# beacon.net
KiCad netlist of a schematic drawn in EAGLE
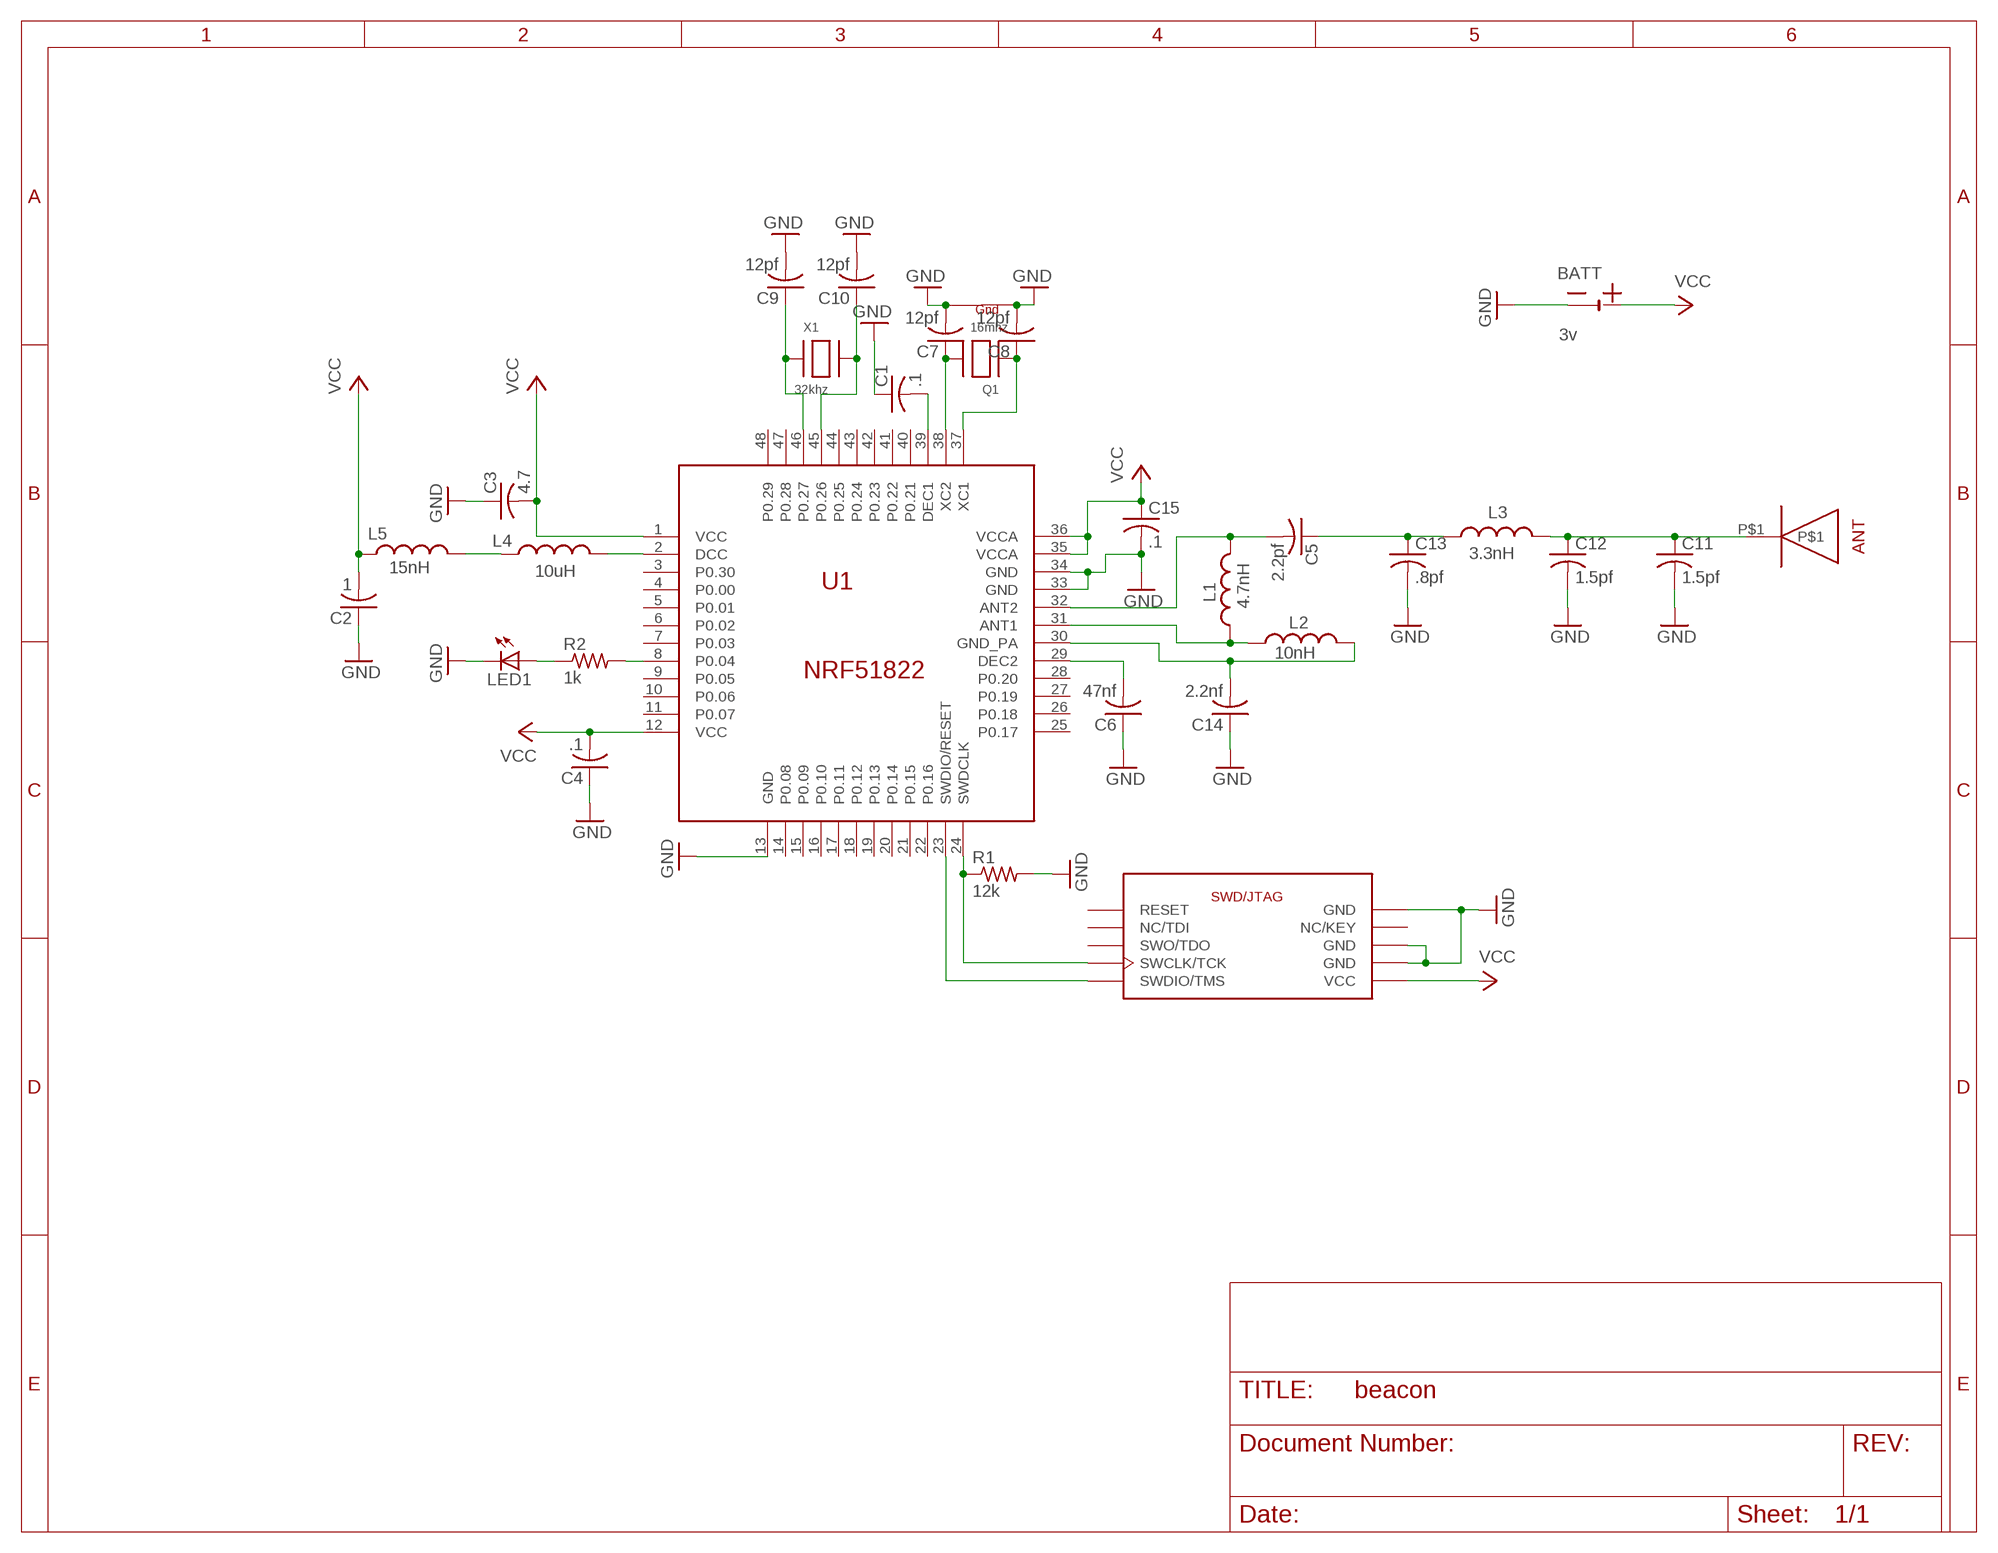
[diagram p0: schematic, sheet 1]

(export (version "E")
  (design (tool "Eeschema 10.0.6"))
  (components
    (comp (ref "BATT")
      (value "3v")
      (footprint "eagle-import:CR2032-SMD")
      (libsource (lib "eagle-import") (part "CR2032SMT"))
    )
    (comp (ref "C1")
      (value ".1")
      (footprint "eagle-import:C0603")
      (libsource (lib "eagle-import") (part "C-USC0603"))
    )
    (comp (ref "C2")
      (value "1")
      (footprint "eagle-import:C0603")
      (libsource (lib "eagle-import") (part "C-USC0603"))
    )
    (comp (ref "C3")
      (value "4.7")
      (footprint "eagle-import:C0603")
      (libsource (lib "eagle-import") (part "C-USC0603"))
    )
    (comp (ref "C4")
      (value ".1")
      (footprint "eagle-import:C0603")
      (libsource (lib "eagle-import") (part "C-USC0603"))
    )
    (comp (ref "C5")
      (value "2.2pf")
      (footprint "eagle-import:C0603")
      (libsource (lib "eagle-import") (part "C-USC0603"))
    )
    (comp (ref "C6")
      (value "47nf")
      (footprint "eagle-import:C0603")
      (libsource (lib "eagle-import") (part "C-USC0603"))
    )
    (comp (ref "C7")
      (value "12pf")
      (footprint "eagle-import:C0603")
      (libsource (lib "eagle-import") (part "C-USC0603"))
    )
    (comp (ref "C8")
      (value "12pf")
      (footprint "eagle-import:C0603")
      (libsource (lib "eagle-import") (part "C-USC0603"))
    )
    (comp (ref "C9")
      (value "12pf")
      (footprint "eagle-import:C0603")
      (libsource (lib "eagle-import") (part "C-USC0603"))
    )
    (comp (ref "C10")
      (value "12pf")
      (footprint "eagle-import:C0603")
      (libsource (lib "eagle-import") (part "C-USC0603"))
    )
    (comp (ref "C11")
      (value "1.5pf")
      (footprint "eagle-import:C0603")
      (libsource (lib "eagle-import") (part "C-USC0603"))
    )
    (comp (ref "C12")
      (value "1.5pf")
      (footprint "eagle-import:C0603")
      (libsource (lib "eagle-import") (part "C-USC0603"))
    )
    (comp (ref "C13")
      (value ".8pf")
      (footprint "eagle-import:C0603")
      (libsource (lib "eagle-import") (part "C-USC0603"))
    )
    (comp (ref "C14")
      (value "2.2nf")
      (footprint "eagle-import:C0603")
      (libsource (lib "eagle-import") (part "C-USC0603"))
    )
    (comp (ref "C15")
      (value ".1")
      (footprint "eagle-import:C0603")
      (libsource (lib "eagle-import") (part "C-USC0603"))
    )
    (comp (ref "L1")
      (value "4.7nH")
      (footprint "eagle-import:0603")
      (libsource (lib "eagle-import") (part "INDUCTOR0603"))
    )
    (comp (ref "L2")
      (value "10nH")
      (footprint "eagle-import:0603")
      (libsource (lib "eagle-import") (part "INDUCTOR0603"))
    )
    (comp (ref "L3")
      (value "3.3nH")
      (footprint "eagle-import:0603")
      (libsource (lib "eagle-import") (part "INDUCTOR0603"))
    )
    (comp (ref "L4")
      (value "10uH")
      (footprint "eagle-import:0603")
      (libsource (lib "eagle-import") (part "INDUCTOR0603"))
    )
    (comp (ref "L5")
      (value "15nH")
      (footprint "eagle-import:0603")
      (libsource (lib "eagle-import") (part "INDUCTOR0603"))
    )
    (comp (ref "LED1")
      (value "LEDCHIP-LED0603")
      (footprint "eagle-import:CHIP-LED0603")
      (libsource (lib "eagle-import") (part "LEDCHIP-LED0603"))
    )
    (comp (ref "Q1")
      (value "16mhz")
      (footprint "eagle-import:NX3225")
      (libsource (lib "eagle-import") (part "XTAL-4-3225"))
    )
    (comp (ref "R1")
      (value "12k")
      (footprint "eagle-import:R0603")
      (libsource (lib "eagle-import") (part "R-US_R0603"))
    )
    (comp (ref "R2")
      (value "1k")
      (footprint "eagle-import:R0603")
      (libsource (lib "eagle-import") (part "R-US_R0603"))
    )
    (comp (ref "U$1")
      (value "SWD_HEADERSWD_SMT")
      (footprint "eagle-import:SWD_SMT")
      (libsource (lib "eagle-import") (part "SWD_HEADERSWD_SMT"))
    )
    (comp (ref "U$2")
      (value "BLE_ANT")
      (footprint "eagle-import:BLE_ANT")
      (libsource (lib "eagle-import") (part "BLE_ANT"))
    )
    (comp (ref "U1")
      (value "NRF51822")
      (footprint "eagle-import:QFN40P600X600X100-49N")
      (libsource (lib "eagle-import") (part "NRF51822"))
    )
    (comp (ref "X1")
      (value "32khz")
      (footprint "eagle-import:XTAL3215")
      (libsource (lib "eagle-import") (part "XTAL-3.2X1.5"))
    )
  )
  (nets
    (net (code "1") (name "GND") (class "Default")
      (node (ref "BATT") (pin "-") (pinfunction "-_-") (pintype "passive"))
      (node (ref "C1") (pin "1") (pinfunction "1_1") (pintype "passive"))
      (node (ref "C10") (pin "2") (pinfunction "2_2") (pintype "passive"))
      (node (ref "C11") (pin "2") (pinfunction "2_2") (pintype "passive"))
      (node (ref "C12") (pin "2") (pinfunction "2_2") (pintype "passive"))
      (node (ref "C13") (pin "2") (pinfunction "2_2") (pintype "passive"))
      (node (ref "C14") (pin "1") (pinfunction "1_1") (pintype "passive"))
      (node (ref "C15") (pin "2") (pinfunction "2_2") (pintype "passive"))
      (node (ref "C2") (pin "1") (pinfunction "1_1") (pintype "passive"))
      (node (ref "C3") (pin "1") (pinfunction "1_1") (pintype "passive"))
      (node (ref "C4") (pin "1") (pinfunction "1_1") (pintype "passive"))
      (node (ref "C6") (pin "1") (pinfunction "1_1") (pintype "passive"))
      (node (ref "C7") (pin "2") (pinfunction "2_2") (pintype "passive"))
      (node (ref "C8") (pin "2") (pinfunction "2_2") (pintype "passive"))
      (node (ref "C9") (pin "2") (pinfunction "2_2") (pintype "passive"))
      (node (ref "LED1") (pin "C") (pinfunction "C_C") (pintype "passive"))
      (node (ref "Q1") (pin "2") (pinfunction "G2_2") (pintype "power_in"))
      (node (ref "Q1") (pin "4") (pinfunction "G1_4") (pintype "power_in"))
      (node (ref "R1") (pin "2") (pinfunction "2_2") (pintype "passive"))
      (node (ref "U$1") (pin "P3") (pinfunction "GND_P3") (pintype "power_in"))
      (node (ref "U$1") (pin "P5") (pinfunction "GND_P5") (pintype "power_in"))
      (node (ref "U$1") (pin "P9") (pinfunction "GND_P9") (pintype "power_in"))
      (node (ref "U1") (pin "13") (pinfunction "GND_13") (pintype "bidirectional"))
      (node (ref "U1") (pin "33") (pinfunction "GND_33") (pintype "bidirectional"))
      (node (ref "U1") (pin "34") (pinfunction "GND_34") (pintype "bidirectional"))
    )
    (net (code "2") (name "Net-(C11-Pad1)") (class "Default")
      (node (ref "C11") (pin "1") (pinfunction "1_1") (pintype "passive"))
      (node (ref "C12") (pin "1") (pinfunction "1_1") (pintype "passive"))
      (node (ref "L3") (pin "2") (pinfunction "2_2") (pintype "passive"))
      (node (ref "U$2") (pin "P$1") (pinfunction "P$1_P$1") (pintype "bidirectional"))
    )
    (net (code "3") (name "Net-(C13-Pad1)") (class "Default")
      (node (ref "C13") (pin "1") (pinfunction "1_1") (pintype "passive"))
      (node (ref "C5") (pin "1") (pinfunction "1_1") (pintype "passive"))
      (node (ref "L3") (pin "1") (pinfunction "1_1") (pintype "passive"))
    )
    (net (code "4") (name "Net-(L4-Pad1)") (class "Default")
      (node (ref "L4") (pin "1") (pinfunction "1_1") (pintype "passive"))
      (node (ref "L5") (pin "2") (pinfunction "2_2") (pintype "passive"))
    )
    (net (code "5") (name "Net-(LED1-PadA)") (class "Default")
      (node (ref "LED1") (pin "A") (pinfunction "A_A") (pintype "passive"))
      (node (ref "R2") (pin "1") (pinfunction "1_1") (pintype "passive"))
    )
    (net (code "6") (name "Net-(Q1-X1)") (class "Default")
      (node (ref "C8") (pin "1") (pinfunction "1_1") (pintype "passive"))
      (node (ref "Q1") (pin "1") (pinfunction "X1_1") (pintype "bidirectional"))
      (node (ref "U1") (pin "37") (pinfunction "XC1_37") (pintype "bidirectional"))
    )
    (net (code "7") (name "Net-(Q1-X2)") (class "Default")
      (node (ref "C7") (pin "1") (pinfunction "1_1") (pintype "passive"))
      (node (ref "Q1") (pin "3") (pinfunction "X2_3") (pintype "bidirectional"))
      (node (ref "U1") (pin "38") (pinfunction "XC2_38") (pintype "bidirectional"))
    )
    (net (code "8") (name "Net-(U$1-SWCLK{slash}TCK)") (class "Default")
      (node (ref "R1") (pin "1") (pinfunction "1_1") (pintype "passive"))
      (node (ref "U$1") (pin "P4") (pinfunction "SWCLK/TCK_P4") (pintype "bidirectional"))
      (node (ref "U1") (pin "24") (pinfunction "SWDCLK_24") (pintype "bidirectional"))
    )
    (net (code "9") (name "Net-(U$1-SWDIO{slash}TMS)") (class "Default")
      (node (ref "U$1") (pin "P2") (pinfunction "SWDIO/TMS_P2") (pintype "bidirectional"))
      (node (ref "U1") (pin "23") (pinfunction "SWDIO/RESET_23") (pintype "bidirectional"))
    )
    (net (code "10") (name "Net-(U1-ANT1)") (class "Default")
      (node (ref "L1") (pin "1") (pinfunction "1_1") (pintype "passive"))
      (node (ref "L2") (pin "1") (pinfunction "1_1") (pintype "passive"))
      (node (ref "U1") (pin "31") (pinfunction "ANT1_31") (pintype "bidirectional"))
    )
    (net (code "11") (name "Net-(U1-ANT2)") (class "Default")
      (node (ref "C5") (pin "2") (pinfunction "2_2") (pintype "passive"))
      (node (ref "L1") (pin "2") (pinfunction "2_2") (pintype "passive"))
      (node (ref "U1") (pin "32") (pinfunction "ANT2_32") (pintype "bidirectional"))
    )
    (net (code "12") (name "Net-(U1-DCC)") (class "Default")
      (node (ref "L4") (pin "2") (pinfunction "2_2") (pintype "passive"))
      (node (ref "U1") (pin "2") (pinfunction "DCC_2") (pintype "bidirectional"))
    )
    (net (code "13") (name "Net-(U1-DEC1)") (class "Default")
      (node (ref "C1") (pin "2") (pinfunction "2_2") (pintype "passive"))
      (node (ref "U1") (pin "39") (pinfunction "DEC1_39") (pintype "bidirectional"))
    )
    (net (code "14") (name "Net-(U1-DEC2)") (class "Default")
      (node (ref "C6") (pin "2") (pinfunction "2_2") (pintype "passive"))
      (node (ref "U1") (pin "29") (pinfunction "DEC2_29") (pintype "bidirectional"))
    )
    (net (code "15") (name "Net-(U1-GND_PA)") (class "Default")
      (node (ref "C14") (pin "2") (pinfunction "2_2") (pintype "passive"))
      (node (ref "L2") (pin "2") (pinfunction "2_2") (pintype "passive"))
      (node (ref "U1") (pin "30") (pinfunction "GND_PA_30") (pintype "bidirectional"))
    )
    (net (code "16") (name "Net-(U1-P0.04)") (class "Default")
      (node (ref "R2") (pin "2") (pinfunction "2_2") (pintype "passive"))
      (node (ref "U1") (pin "8") (pinfunction "P0.04_8") (pintype "bidirectional"))
    )
    (net (code "17") (name "Net-(U1-P0.26)") (class "Default")
      (node (ref "C10") (pin "1") (pinfunction "1_1") (pintype "passive"))
      (node (ref "U1") (pin "45") (pinfunction "P0.26_45") (pintype "bidirectional"))
      (node (ref "X1") (pin "P$2") (pinfunction "P$2_P$2") (pintype "bidirectional"))
    )
    (net (code "18") (name "Net-(U1-P0.27)") (class "Default")
      (node (ref "C9") (pin "1") (pinfunction "1_1") (pintype "passive"))
      (node (ref "U1") (pin "46") (pinfunction "P0.27_46") (pintype "bidirectional"))
      (node (ref "X1") (pin "P$1") (pinfunction "P$1_P$1") (pintype "bidirectional"))
    )
    (net (code "19") (name "VCC") (class "Default")
      (node (ref "BATT") (pin "+$1") (pinfunction "+1_+$1") (pintype "passive"))
      (node (ref "BATT") (pin "+$2") (pinfunction "+1_+$2") (pintype "passive"))
      (node (ref "C15") (pin "1") (pinfunction "1_1") (pintype "passive"))
      (node (ref "C2") (pin "2") (pinfunction "2_2") (pintype "passive"))
      (node (ref "C3") (pin "2") (pinfunction "2_2") (pintype "passive"))
      (node (ref "C4") (pin "2") (pinfunction "2_2") (pintype "passive"))
      (node (ref "L5") (pin "1") (pinfunction "1_1") (pintype "passive"))
      (node (ref "U$1") (pin "P1") (pinfunction "VCC_P1") (pintype "power_in"))
      (node (ref "U1") (pin "1") (pinfunction "VCC_1") (pintype "bidirectional"))
      (node (ref "U1") (pin "12") (pinfunction "VCC_12") (pintype "bidirectional"))
      (node (ref "U1") (pin "35") (pinfunction "VCCA_35") (pintype "bidirectional"))
      (node (ref "U1") (pin "36") (pinfunction "VCCA_36") (pintype "bidirectional"))
    )
    (net (code "20") (name "unconnected-(U$1-NC{slash}KEY-PadP7)") (class "Default")
      (node (ref "U$1") (pin "P7") (pinfunction "NC/KEY_P7") (pintype "no_connect"))
    )
    (net (code "21") (name "unconnected-(U$1-NC{slash}TDI-PadP8)") (class "Default")
      (node (ref "U$1") (pin "P8") (pinfunction "NC/TDI_P8") (pintype "bidirectional"))
    )
    (net (code "22") (name "unconnected-(U$1-RESET-PadP10)") (class "Default")
      (node (ref "U$1") (pin "P10") (pinfunction "RESET_P10") (pintype "bidirectional"))
    )
    (net (code "23") (name "unconnected-(U$1-SWO{slash}TDO-PadP6)") (class "Default")
      (node (ref "U$1") (pin "P6") (pinfunction "SWO/TDO_P6") (pintype "bidirectional"))
    )
    (net (code "24") (name "unconnected-(U1-P0.00-Pad4)") (class "Default")
      (node (ref "U1") (pin "4") (pinfunction "P0.00_4") (pintype "bidirectional"))
    )
    (net (code "25") (name "unconnected-(U1-P0.01-Pad5)") (class "Default")
      (node (ref "U1") (pin "5") (pinfunction "P0.01_5") (pintype "bidirectional"))
    )
    (net (code "26") (name "unconnected-(U1-P0.02-Pad6)") (class "Default")
      (node (ref "U1") (pin "6") (pinfunction "P0.02_6") (pintype "bidirectional"))
    )
    (net (code "27") (name "unconnected-(U1-P0.03-Pad7)") (class "Default")
      (node (ref "U1") (pin "7") (pinfunction "P0.03_7") (pintype "bidirectional"))
    )
    (net (code "28") (name "unconnected-(U1-P0.05-Pad9)") (class "Default")
      (node (ref "U1") (pin "9") (pinfunction "P0.05_9") (pintype "bidirectional"))
    )
    (net (code "29") (name "unconnected-(U1-P0.06-Pad10)") (class "Default")
      (node (ref "U1") (pin "10") (pinfunction "P0.06_10") (pintype "bidirectional"))
    )
    (net (code "30") (name "unconnected-(U1-P0.07-Pad11)") (class "Default")
      (node (ref "U1") (pin "11") (pinfunction "P0.07_11") (pintype "bidirectional"))
    )
    (net (code "31") (name "unconnected-(U1-P0.08-Pad14)") (class "Default")
      (node (ref "U1") (pin "14") (pinfunction "P0.08_14") (pintype "bidirectional"))
    )
    (net (code "32") (name "unconnected-(U1-P0.09-Pad15)") (class "Default")
      (node (ref "U1") (pin "15") (pinfunction "P0.09_15") (pintype "bidirectional"))
    )
    (net (code "33") (name "unconnected-(U1-P0.10-Pad16)") (class "Default")
      (node (ref "U1") (pin "16") (pinfunction "P0.10_16") (pintype "bidirectional"))
    )
    (net (code "34") (name "unconnected-(U1-P0.11-Pad17)") (class "Default")
      (node (ref "U1") (pin "17") (pinfunction "P0.11_17") (pintype "bidirectional"))
    )
    (net (code "35") (name "unconnected-(U1-P0.12-Pad18)") (class "Default")
      (node (ref "U1") (pin "18") (pinfunction "P0.12_18") (pintype "bidirectional"))
    )
    (net (code "36") (name "unconnected-(U1-P0.13-Pad19)") (class "Default")
      (node (ref "U1") (pin "19") (pinfunction "P0.13_19") (pintype "bidirectional"))
    )
    (net (code "37") (name "unconnected-(U1-P0.14-Pad20)") (class "Default")
      (node (ref "U1") (pin "20") (pinfunction "P0.14_20") (pintype "bidirectional"))
    )
    (net (code "38") (name "unconnected-(U1-P0.15-Pad21)") (class "Default")
      (node (ref "U1") (pin "21") (pinfunction "P0.15_21") (pintype "bidirectional"))
    )
    (net (code "39") (name "unconnected-(U1-P0.16-Pad22)") (class "Default")
      (node (ref "U1") (pin "22") (pinfunction "P0.16_22") (pintype "bidirectional"))
    )
    (net (code "40") (name "unconnected-(U1-P0.17-Pad25)") (class "Default")
      (node (ref "U1") (pin "25") (pinfunction "P0.17_25") (pintype "bidirectional"))
    )
    (net (code "41") (name "unconnected-(U1-P0.18-Pad26)") (class "Default")
      (node (ref "U1") (pin "26") (pinfunction "P0.18_26") (pintype "bidirectional"))
    )
    (net (code "42") (name "unconnected-(U1-P0.19-Pad27)") (class "Default")
      (node (ref "U1") (pin "27") (pinfunction "P0.19_27") (pintype "bidirectional"))
    )
    (net (code "43") (name "unconnected-(U1-P0.20-Pad28)") (class "Default")
      (node (ref "U1") (pin "28") (pinfunction "P0.20_28") (pintype "bidirectional"))
    )
    (net (code "44") (name "unconnected-(U1-P0.21-Pad40)") (class "Default")
      (node (ref "U1") (pin "40") (pinfunction "P0.21_40") (pintype "bidirectional"))
    )
    (net (code "45") (name "unconnected-(U1-P0.22-Pad41)") (class "Default")
      (node (ref "U1") (pin "41") (pinfunction "P0.22_41") (pintype "bidirectional"))
    )
    (net (code "46") (name "unconnected-(U1-P0.23-Pad42)") (class "Default")
      (node (ref "U1") (pin "42") (pinfunction "P0.23_42") (pintype "bidirectional"))
    )
    (net (code "47") (name "unconnected-(U1-P0.24-Pad43)") (class "Default")
      (node (ref "U1") (pin "43") (pinfunction "P0.24_43") (pintype "bidirectional"))
    )
    (net (code "48") (name "unconnected-(U1-P0.25-Pad44)") (class "Default")
      (node (ref "U1") (pin "44") (pinfunction "P0.25_44") (pintype "bidirectional"))
    )
    (net (code "49") (name "unconnected-(U1-P0.28-Pad47)") (class "Default")
      (node (ref "U1") (pin "47") (pinfunction "P0.28_47") (pintype "bidirectional"))
    )
    (net (code "50") (name "unconnected-(U1-P0.29-Pad48)") (class "Default")
      (node (ref "U1") (pin "48") (pinfunction "P0.29_48") (pintype "bidirectional"))
    )
    (net (code "51") (name "unconnected-(U1-P0.30-Pad3)") (class "Default")
      (node (ref "U1") (pin "3") (pinfunction "P0.30_3") (pintype "bidirectional"))
    )
  )
)
